# motordriver.net
KiCad netlist of a schematic drawn in EAGLE
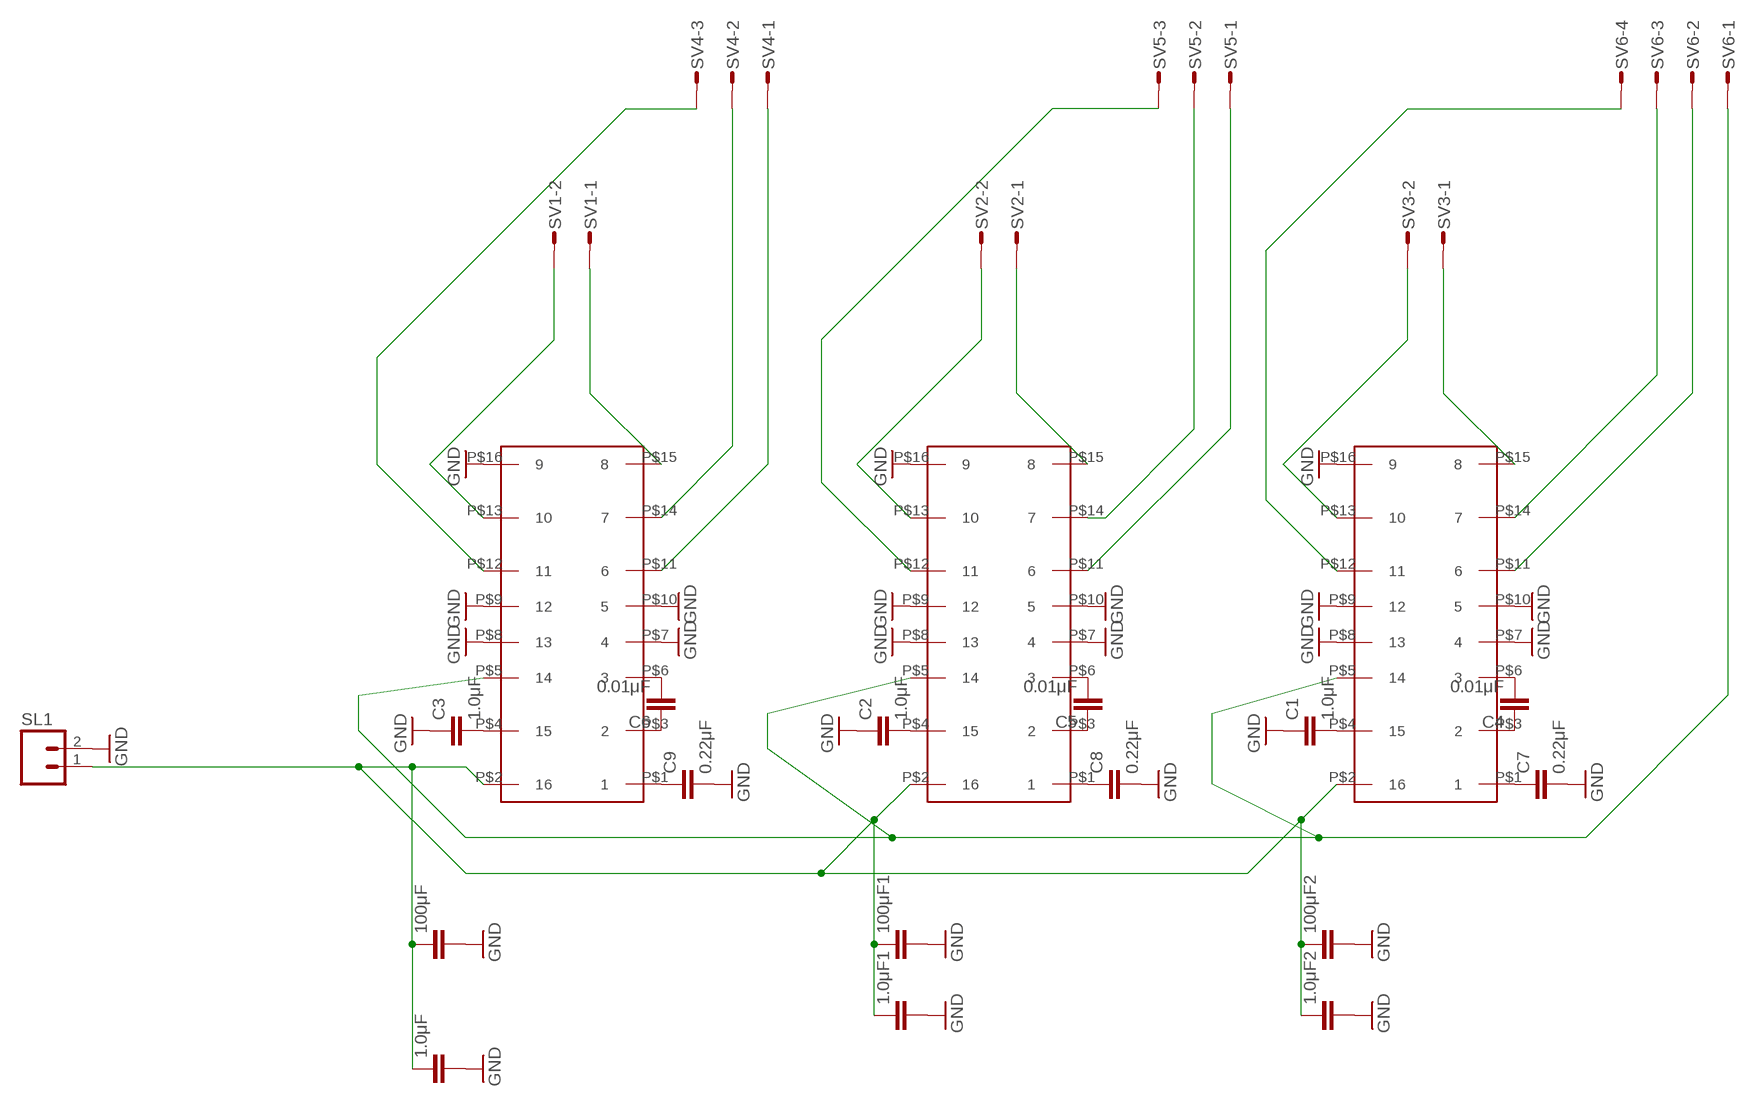
[diagram p0: schematic, sheet 1]

(export (version "E")
  (design (tool "Eeschema 10.0.6"))
  (components
    (comp (ref "1.0μF")
      (value "C-EU025-024X044")
      (footprint "eagle-import:C025-024X044")
      (libsource (lib "eagle-import") (part "C-EU025-024X044"))
    )
    (comp (ref "1.0μF1")
      (value "C-EU025-024X044")
      (footprint "eagle-import:C025-024X044")
      (libsource (lib "eagle-import") (part "C-EU025-024X044"))
    )
    (comp (ref "1.0μF2")
      (value "C-EU025-024X044")
      (footprint "eagle-import:C025-024X044")
      (libsource (lib "eagle-import") (part "C-EU025-024X044"))
    )
    (comp (ref "100μF")
      (value "C-EU025-024X044")
      (footprint "eagle-import:C025-024X044")
      (libsource (lib "eagle-import") (part "C-EU025-024X044"))
    )
    (comp (ref "100μF1")
      (value "C-EU025-024X044")
      (footprint "eagle-import:C025-024X044")
      (libsource (lib "eagle-import") (part "C-EU025-024X044"))
    )
    (comp (ref "100μF2")
      (value "C-EU025-024X044")
      (footprint "eagle-import:C025-024X044")
      (libsource (lib "eagle-import") (part "C-EU025-024X044"))
    )
    (comp (ref "C1")
      (value "1.0μF")
      (footprint "eagle-import:C025-024X044")
      (libsource (lib "eagle-import") (part "C-EU025-024X044"))
    )
    (comp (ref "C2")
      (value "1.0μF")
      (footprint "eagle-import:C025-024X044")
      (libsource (lib "eagle-import") (part "C-EU025-024X044"))
    )
    (comp (ref "C3")
      (value "1.0μF")
      (footprint "eagle-import:C025-024X044")
      (libsource (lib "eagle-import") (part "C-EU025-024X044"))
    )
    (comp (ref "C4")
      (value "0.01μF")
      (footprint "eagle-import:C025-024X044")
      (libsource (lib "eagle-import") (part "C-EU025-024X044"))
    )
    (comp (ref "C5")
      (value "0.01μF")
      (footprint "eagle-import:C025-024X044")
      (libsource (lib "eagle-import") (part "C-EU025-024X044"))
    )
    (comp (ref "C6")
      (value "0.01μF")
      (footprint "eagle-import:C025-024X044")
      (libsource (lib "eagle-import") (part "C-EU025-024X044"))
    )
    (comp (ref "C7")
      (value "0.22μF")
      (footprint "eagle-import:C025-024X044")
      (libsource (lib "eagle-import") (part "C-EU025-024X044"))
    )
    (comp (ref "C8")
      (value "0.22μF")
      (footprint "eagle-import:C025-024X044")
      (libsource (lib "eagle-import") (part "C-EU025-024X044"))
    )
    (comp (ref "C9")
      (value "0.22μF")
      (footprint "eagle-import:C025-024X044")
      (libsource (lib "eagle-import") (part "C-EU025-024X044"))
    )
    (comp (ref "SL1")
      (value "M02")
      (footprint "eagle-import:02P")
      (libsource (lib "eagle-import") (part "M02"))
    )
    (comp (ref "SV1")
      (value "L02P")
      (footprint "eagle-import:L02P")
      (libsource (lib "eagle-import") (part "L02P"))
    )
    (comp (ref "SV2")
      (value "L02P")
      (footprint "eagle-import:L02P")
      (libsource (lib "eagle-import") (part "L02P"))
    )
    (comp (ref "SV3")
      (value "L02P")
      (footprint "eagle-import:L02P")
      (libsource (lib "eagle-import") (part "L02P"))
    )
    (comp (ref "SV4")
      (value "S03P")
      (footprint "eagle-import:S03P")
      (libsource (lib "eagle-import") (part "S03P"))
    )
    (comp (ref "SV5")
      (value "S03P")
      (footprint "eagle-import:S03P")
      (libsource (lib "eagle-import") (part "S03P"))
    )
    (comp (ref "SV6")
      (value "S04P")
      (footprint "eagle-import:S04P")
      (libsource (lib "eagle-import") (part "S04P"))
    )
    (comp (ref "U$1")
      (value "TB6549PG")
      (footprint "eagle-import:TB6549PG")
      (libsource (lib "eagle-import") (part "TB6549PG"))
    )
    (comp (ref "U$2")
      (value "TB6549PG")
      (footprint "eagle-import:TB6549PG")
      (libsource (lib "eagle-import") (part "TB6549PG"))
    )
    (comp (ref "U$3")
      (value "TB6549PG")
      (footprint "eagle-import:TB6549PG")
      (libsource (lib "eagle-import") (part "TB6549PG"))
    )
  )
  (nets
    (net (code "1") (name "GND") (class "Default")
      (node (ref "1.0μF") (pin "2") (pinfunction "2_2") (pintype "passive"))
      (node (ref "1.0μF1") (pin "2") (pinfunction "2_2") (pintype "passive"))
      (node (ref "1.0μF2") (pin "2") (pinfunction "2_2") (pintype "passive"))
      (node (ref "100μF") (pin "2") (pinfunction "2_2") (pintype "passive"))
      (node (ref "100μF1") (pin "2") (pinfunction "2_2") (pintype "passive"))
      (node (ref "100μF2") (pin "2") (pinfunction "2_2") (pintype "passive"))
      (node (ref "C1") (pin "1") (pinfunction "1_1") (pintype "passive"))
      (node (ref "C2") (pin "1") (pinfunction "1_1") (pintype "passive"))
      (node (ref "C3") (pin "1") (pinfunction "1_1") (pintype "passive"))
      (node (ref "C7") (pin "2") (pinfunction "2_2") (pintype "passive"))
      (node (ref "C8") (pin "2") (pinfunction "2_2") (pintype "passive"))
      (node (ref "C9") (pin "2") (pinfunction "2_2") (pintype "passive"))
      (node (ref "SL1") (pin "2") (pinfunction "2_2") (pintype "passive"))
      (node (ref "U$1") (pin "P$10") (pinfunction "5_P$10") (pintype "bidirectional"))
      (node (ref "U$1") (pin "P$16") (pinfunction "9_P$16") (pintype "bidirectional"))
      (node (ref "U$1") (pin "P$7") (pinfunction "4_P$7") (pintype "bidirectional"))
      (node (ref "U$1") (pin "P$8") (pinfunction "13_P$8") (pintype "bidirectional"))
      (node (ref "U$1") (pin "P$9") (pinfunction "12_P$9") (pintype "bidirectional"))
      (node (ref "U$2") (pin "P$10") (pinfunction "5_P$10") (pintype "bidirectional"))
      (node (ref "U$2") (pin "P$16") (pinfunction "9_P$16") (pintype "bidirectional"))
      (node (ref "U$2") (pin "P$7") (pinfunction "4_P$7") (pintype "bidirectional"))
      (node (ref "U$2") (pin "P$8") (pinfunction "13_P$8") (pintype "bidirectional"))
      (node (ref "U$2") (pin "P$9") (pinfunction "12_P$9") (pintype "bidirectional"))
      (node (ref "U$3") (pin "P$10") (pinfunction "5_P$10") (pintype "bidirectional"))
      (node (ref "U$3") (pin "P$16") (pinfunction "9_P$16") (pintype "bidirectional"))
      (node (ref "U$3") (pin "P$7") (pinfunction "4_P$7") (pintype "bidirectional"))
      (node (ref "U$3") (pin "P$8") (pinfunction "13_P$8") (pintype "bidirectional"))
      (node (ref "U$3") (pin "P$9") (pinfunction "12_P$9") (pintype "bidirectional"))
    )
    (net (code "2") (name "Net-(SV1A-S)") (class "Default")
      (node (ref "SV1") (pin "1") (pinfunction "S_1") (pintype "passive"))
      (node (ref "U$1") (pin "P$15") (pinfunction "8_P$15") (pintype "bidirectional"))
    )
    (net (code "3") (name "Net-(SV1B-S)") (class "Default")
      (node (ref "SV1") (pin "2") (pinfunction "S_2") (pintype "passive"))
      (node (ref "U$1") (pin "P$13") (pinfunction "10_P$13") (pintype "bidirectional"))
    )
    (net (code "4") (name "Net-(SV2A-S)") (class "Default")
      (node (ref "SV2") (pin "1") (pinfunction "S_1") (pintype "passive"))
      (node (ref "U$2") (pin "P$15") (pinfunction "8_P$15") (pintype "bidirectional"))
    )
    (net (code "5") (name "Net-(SV2B-S)") (class "Default")
      (node (ref "SV2") (pin "2") (pinfunction "S_2") (pintype "passive"))
      (node (ref "U$2") (pin "P$13") (pinfunction "10_P$13") (pintype "bidirectional"))
    )
    (net (code "6") (name "Net-(SV3A-S)") (class "Default")
      (node (ref "SV3") (pin "1") (pinfunction "S_1") (pintype "passive"))
      (node (ref "U$3") (pin "P$15") (pinfunction "8_P$15") (pintype "bidirectional"))
    )
    (net (code "7") (name "Net-(SV3B-S)") (class "Default")
      (node (ref "SV3") (pin "2") (pinfunction "S_2") (pintype "passive"))
      (node (ref "U$3") (pin "P$13") (pinfunction "10_P$13") (pintype "bidirectional"))
    )
    (net (code "8") (name "Net-(SV4A-S)") (class "Default")
      (node (ref "SV4") (pin "1") (pinfunction "S_1") (pintype "passive"))
      (node (ref "U$1") (pin "P$11") (pinfunction "6_P$11") (pintype "bidirectional"))
    )
    (net (code "9") (name "Net-(SV4B-S)") (class "Default")
      (node (ref "SV4") (pin "2") (pinfunction "S_2") (pintype "passive"))
      (node (ref "U$1") (pin "P$14") (pinfunction "7_P$14") (pintype "bidirectional"))
    )
    (net (code "10") (name "Net-(SV4C-S)") (class "Default")
      (node (ref "SV4") (pin "3") (pinfunction "S_3") (pintype "passive"))
      (node (ref "U$1") (pin "P$12") (pinfunction "11_P$12") (pintype "bidirectional"))
    )
    (net (code "11") (name "Net-(SV5A-S)") (class "Default")
      (node (ref "SV5") (pin "1") (pinfunction "S_1") (pintype "passive"))
      (node (ref "U$2") (pin "P$11") (pinfunction "6_P$11") (pintype "bidirectional"))
    )
    (net (code "12") (name "Net-(SV5B-S)") (class "Default")
      (node (ref "SV5") (pin "2") (pinfunction "S_2") (pintype "passive"))
      (node (ref "U$2") (pin "P$14") (pinfunction "7_P$14") (pintype "bidirectional"))
    )
    (net (code "13") (name "Net-(SV5C-S)") (class "Default")
      (node (ref "SV5") (pin "3") (pinfunction "S_3") (pintype "passive"))
      (node (ref "U$2") (pin "P$12") (pinfunction "11_P$12") (pintype "bidirectional"))
    )
    (net (code "14") (name "Net-(SV6A-S)") (class "Default")
      (node (ref "SV6") (pin "1") (pinfunction "S_1") (pintype "passive"))
      (node (ref "U$1") (pin "P$5") (pinfunction "14_P$5") (pintype "bidirectional"))
      (node (ref "U$2") (pin "P$5") (pinfunction "14_P$5") (pintype "bidirectional"))
      (node (ref "U$3") (pin "P$5") (pinfunction "14_P$5") (pintype "bidirectional"))
    )
    (net (code "15") (name "Net-(SV6B-S)") (class "Default")
      (node (ref "SV6") (pin "2") (pinfunction "S_2") (pintype "passive"))
      (node (ref "U$3") (pin "P$11") (pinfunction "6_P$11") (pintype "bidirectional"))
    )
    (net (code "16") (name "Net-(SV6C-S)") (class "Default")
      (node (ref "SV6") (pin "3") (pinfunction "S_3") (pintype "passive"))
      (node (ref "U$3") (pin "P$14") (pinfunction "7_P$14") (pintype "bidirectional"))
    )
    (net (code "17") (name "Net-(SV6D-S)") (class "Default")
      (node (ref "SV6") (pin "4") (pinfunction "S_4") (pintype "passive"))
      (node (ref "U$3") (pin "P$12") (pinfunction "11_P$12") (pintype "bidirectional"))
    )
    (net (code "18") (name "Net-(U$1-1)") (class "Default")
      (node (ref "C9") (pin "1") (pinfunction "1_1") (pintype "passive"))
      (node (ref "U$1") (pin "P$1") (pinfunction "1_P$1") (pintype "bidirectional"))
    )
    (net (code "19") (name "Net-(U$1-2)") (class "Default")
      (node (ref "C6") (pin "1") (pinfunction "1_1") (pintype "passive"))
      (node (ref "U$1") (pin "P$3") (pinfunction "2_P$3") (pintype "bidirectional"))
    )
    (net (code "20") (name "Net-(U$1-3)") (class "Default")
      (node (ref "C6") (pin "2") (pinfunction "2_2") (pintype "passive"))
      (node (ref "U$1") (pin "P$6") (pinfunction "3_P$6") (pintype "bidirectional"))
    )
    (net (code "21") (name "Net-(U$1-15)") (class "Default")
      (node (ref "C3") (pin "2") (pinfunction "2_2") (pintype "passive"))
      (node (ref "U$1") (pin "P$4") (pinfunction "15_P$4") (pintype "bidirectional"))
    )
    (net (code "22") (name "Net-(U$1-16)") (class "Default")
      (node (ref "1.0μF") (pin "1") (pinfunction "1_1") (pintype "passive"))
      (node (ref "1.0μF1") (pin "1") (pinfunction "1_1") (pintype "passive"))
      (node (ref "1.0μF2") (pin "1") (pinfunction "1_1") (pintype "passive"))
      (node (ref "100μF") (pin "1") (pinfunction "1_1") (pintype "passive"))
      (node (ref "100μF1") (pin "1") (pinfunction "1_1") (pintype "passive"))
      (node (ref "100μF2") (pin "1") (pinfunction "1_1") (pintype "passive"))
      (node (ref "SL1") (pin "1") (pinfunction "1_1") (pintype "passive"))
      (node (ref "U$1") (pin "P$2") (pinfunction "16_P$2") (pintype "bidirectional"))
      (node (ref "U$2") (pin "P$2") (pinfunction "16_P$2") (pintype "bidirectional"))
      (node (ref "U$3") (pin "P$2") (pinfunction "16_P$2") (pintype "bidirectional"))
    )
    (net (code "23") (name "Net-(U$2-1)") (class "Default")
      (node (ref "C8") (pin "1") (pinfunction "1_1") (pintype "passive"))
      (node (ref "U$2") (pin "P$1") (pinfunction "1_P$1") (pintype "bidirectional"))
    )
    (net (code "24") (name "Net-(U$2-2)") (class "Default")
      (node (ref "C5") (pin "1") (pinfunction "1_1") (pintype "passive"))
      (node (ref "U$2") (pin "P$3") (pinfunction "2_P$3") (pintype "bidirectional"))
    )
    (net (code "25") (name "Net-(U$2-3)") (class "Default")
      (node (ref "C5") (pin "2") (pinfunction "2_2") (pintype "passive"))
      (node (ref "U$2") (pin "P$6") (pinfunction "3_P$6") (pintype "bidirectional"))
    )
    (net (code "26") (name "Net-(U$2-15)") (class "Default")
      (node (ref "C2") (pin "2") (pinfunction "2_2") (pintype "passive"))
      (node (ref "U$2") (pin "P$4") (pinfunction "15_P$4") (pintype "bidirectional"))
    )
    (net (code "27") (name "Net-(U$3-1)") (class "Default")
      (node (ref "C7") (pin "1") (pinfunction "1_1") (pintype "passive"))
      (node (ref "U$3") (pin "P$1") (pinfunction "1_P$1") (pintype "bidirectional"))
    )
    (net (code "28") (name "Net-(U$3-2)") (class "Default")
      (node (ref "C4") (pin "1") (pinfunction "1_1") (pintype "passive"))
      (node (ref "U$3") (pin "P$3") (pinfunction "2_P$3") (pintype "bidirectional"))
    )
    (net (code "29") (name "Net-(U$3-3)") (class "Default")
      (node (ref "C4") (pin "2") (pinfunction "2_2") (pintype "passive"))
      (node (ref "U$3") (pin "P$6") (pinfunction "3_P$6") (pintype "bidirectional"))
    )
    (net (code "30") (name "Net-(U$3-15)") (class "Default")
      (node (ref "C1") (pin "2") (pinfunction "2_2") (pintype "passive"))
      (node (ref "U$3") (pin "P$4") (pinfunction "15_P$4") (pintype "bidirectional"))
    )
  )
)
